# AName.net
KiCad netlist of a schematic drawn in EAGLE
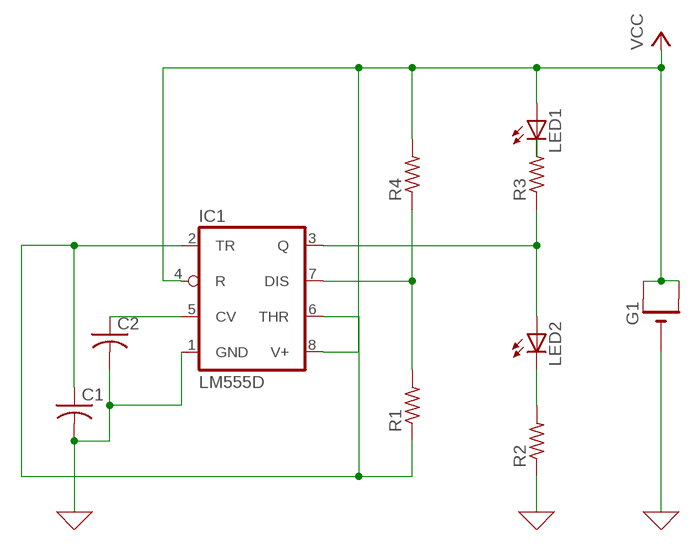
[diagram p0: schematic, sheet 1]

(export (version "E")
  (design (tool "Eeschema 10.0.6"))
  (components
    (comp (ref "C1")
      (value "C-USC0805")
      (footprint "eagle-import:C0805")
      (libsource (lib "eagle-import") (part "C-USC0805"))
    )
    (comp (ref "C2")
      (value "C-USC0805")
      (footprint "eagle-import:C0805")
      (libsource (lib "eagle-import") (part "C-USC0805"))
    )
    (comp (ref "G1")
      (value "CR1220THM")
      (footprint "eagle-import:CR1220-THM")
      (libsource (lib "eagle-import") (part "CR1220THM"))
    )
    (comp (ref "IC1")
      (value "LM555D")
      (footprint "eagle-import:SO08")
      (libsource (lib "eagle-import") (part "555DLM"))
    )
    (comp (ref "LED1")
      (value "LED5MM")
      (footprint "eagle-import:LED5MM")
      (libsource (lib "eagle-import") (part "LED5MM"))
    )
    (comp (ref "LED2")
      (value "LED5MM")
      (footprint "eagle-import:LED5MM")
      (libsource (lib "eagle-import") (part "LED5MM"))
    )
    (comp (ref "R1")
      (value "R-US_R0805")
      (footprint "eagle-import:R0805")
      (libsource (lib "eagle-import") (part "rcl_334_R-US_R0805"))
    )
    (comp (ref "R2")
      (value "R-US_R0805")
      (footprint "eagle-import:R0805")
      (libsource (lib "eagle-import") (part "rcl_334_R-US_R0805"))
    )
    (comp (ref "R3")
      (value "R-US_M0805")
      (footprint "eagle-import:M0805")
      (libsource (lib "eagle-import") (part "R-US_M0805"))
    )
    (comp (ref "R4")
      (value "R-US_R0805")
      (footprint "eagle-import:R0805")
      (libsource (lib "eagle-import") (part "rcl_334_R-US_R0805"))
    )
  )
  (nets
    (net (code "1") (name "GND") (class "Default")
      (node (ref "C1") (pin "2") (pinfunction "2_2") (pintype "passive"))
      (node (ref "C2") (pin "2") (pinfunction "2_2") (pintype "passive"))
      (node (ref "G1") (pin "-") (pinfunction "-_-") (pintype "passive"))
      (node (ref "IC1") (pin "1") (pinfunction "GND_1") (pintype "power_in"))
      (node (ref "R2") (pin "1") (pinfunction "1_1") (pintype "passive"))
    )
    (net (code "2") (name "Net-(IC1-CV)") (class "Default")
      (node (ref "C2") (pin "1") (pinfunction "1_1") (pintype "passive"))
      (node (ref "IC1") (pin "5") (pinfunction "CV_5") (pintype "input"))
    )
    (net (code "3") (name "Net-(IC1-DIS)") (class "Default")
      (node (ref "IC1") (pin "7") (pinfunction "DIS_7") (pintype "input"))
      (node (ref "R1") (pin "2") (pinfunction "2_2") (pintype "passive"))
      (node (ref "R4") (pin "1") (pinfunction "1_1") (pintype "passive"))
    )
    (net (code "4") (name "Net-(IC1-Q)") (class "Default")
      (node (ref "IC1") (pin "3") (pinfunction "Q_3") (pintype "output"))
      (node (ref "LED2") (pin "A") (pinfunction "A_A") (pintype "passive"))
      (node (ref "R3") (pin "1") (pinfunction "1_1") (pintype "passive"))
    )
    (net (code "5") (name "Net-(IC1-THR)") (class "Default")
      (node (ref "C1") (pin "1") (pinfunction "1_1") (pintype "passive"))
      (node (ref "IC1") (pin "2") (pinfunction "TR_2") (pintype "input"))
      (node (ref "IC1") (pin "6") (pinfunction "THR_6") (pintype "input"))
      (node (ref "R1") (pin "1") (pinfunction "1_1") (pintype "passive"))
    )
    (net (code "6") (name "Net-(LED1-C)") (class "Default")
      (node (ref "LED1") (pin "K") (pinfunction "C_K") (pintype "passive"))
      (node (ref "R3") (pin "2") (pinfunction "2_2") (pintype "passive"))
    )
    (net (code "7") (name "Net-(LED2-C)") (class "Default")
      (node (ref "LED2") (pin "K") (pinfunction "C_K") (pintype "passive"))
      (node (ref "R2") (pin "2") (pinfunction "2_2") (pintype "passive"))
    )
    (net (code "8") (name "VCC") (class "Default")
      (node (ref "G1") (pin "+1") (pinfunction "+_+1") (pintype "passive"))
      (node (ref "G1") (pin "+2") (pinfunction "+1_+2") (pintype "passive"))
      (node (ref "IC1") (pin "4") (pinfunction "R_4") (pintype "input"))
      (node (ref "IC1") (pin "8") (pinfunction "V+_8") (pintype "power_in"))
      (node (ref "LED1") (pin "A") (pinfunction "A_A") (pintype "passive"))
      (node (ref "R4") (pin "2") (pinfunction "2_2") (pintype "passive"))
    )
  )
)
